# Microcontroller.net
KiCad netlist of a schematic drawn in EAGLE
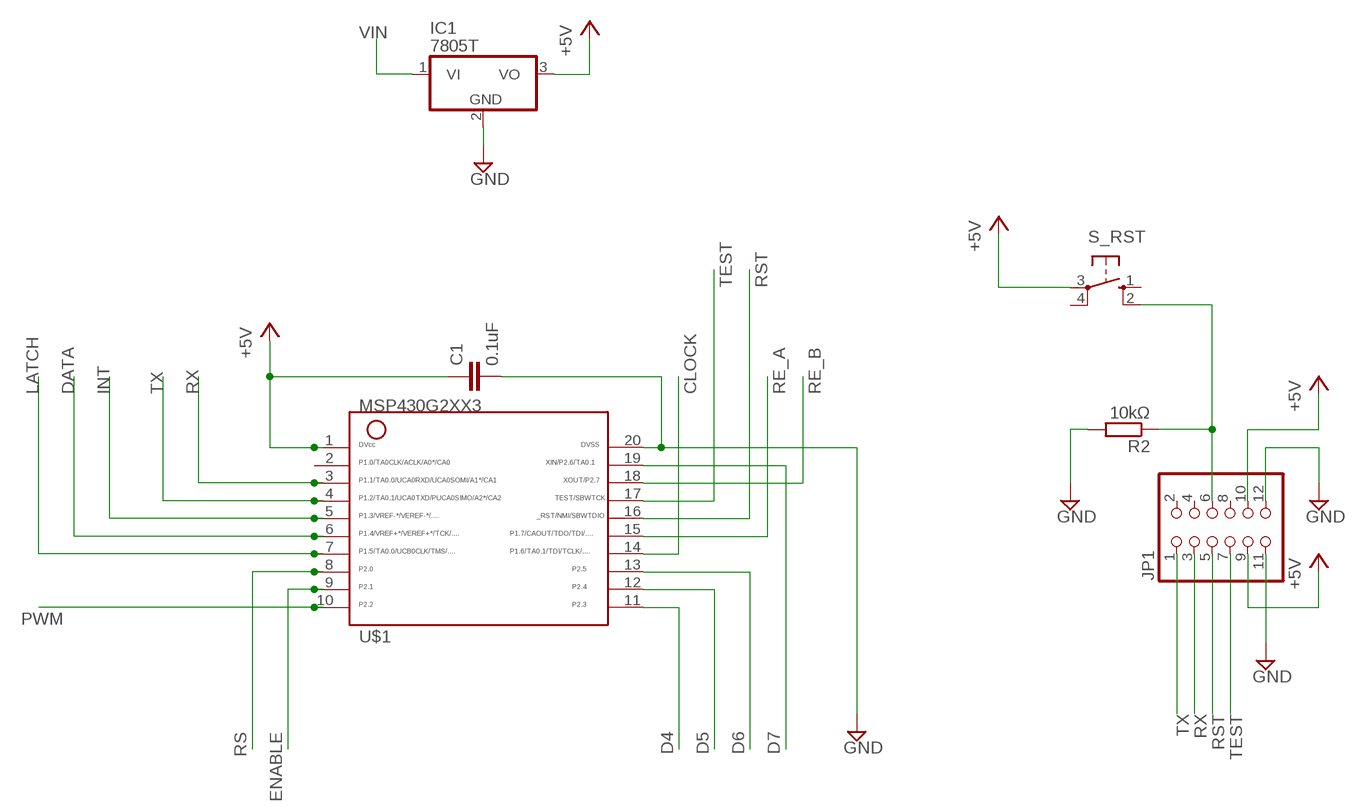
[diagram p0: schematic, sheet 1]

(export (version "E")
  (design (tool "Eeschema 10.0.6"))
  (components
    (comp (ref "C1")
      (value "0.1uF")
      (footprint "eagle-import:C025-025X050")
      (libsource (lib "eagle-import") (part "C-EU025-025X050"))
    )
    (comp (ref "IC1")
      (value "7805T")
      (footprint "eagle-import:TO220H")
      (libsource (lib "eagle-import") (part "78T05"))
    )
    (comp (ref "JP1")
      (value "PINHD-2X6")
      (footprint "eagle-import:2X06")
      (libsource (lib "eagle-import") (part "PINHD-2X6"))
    )
    (comp (ref "R2")
      (value "10kΩ")
      (footprint "eagle-import:0207_10")
      (libsource (lib "eagle-import") (part "R-EU_0207/10"))
    )
    (comp (ref "S_RST")
      (value "10-XX")
      (footprint "eagle-import:B3F-10XX")
      (fields (field (name "MPN") "B3F-1000"))
      (libsource (lib "eagle-import") (part "10-XX"))
    )
    (comp (ref "U$1")
      (value "G2XX3---N20")
      (footprint "eagle-import:N20")
      (libsource (lib "eagle-import") (part "G2XX3---N20"))
    )
  )
  (nets
    (net (code "1") (name "+5V") (class "Default")
      (node (ref "C1") (pin "1") (pinfunction "1_1") (pintype "passive"))
      (node (ref "IC1") (pin "3") (pinfunction "VO_3") (pintype "passive"))
      (node (ref "JP1") (pin "10") (pinfunction "10_10") (pintype "passive"))
      (node (ref "JP1") (pin "9") (pinfunction "9_9") (pintype "passive"))
      (node (ref "S_RST") (pin "3") (pinfunction "P_3") (pintype "passive"))
      (node (ref "U$1") (pin "1") (pinfunction "1_1") (pintype "bidirectional"))
    )
    (net (code "2") (name "/CLOCK") (class "Default")
      (node (ref "U$1") (pin "14") (pinfunction "14_14") (pintype "bidirectional"))
    )
    (net (code "3") (name "/D4") (class "Default")
      (node (ref "U$1") (pin "11") (pinfunction "11_11") (pintype "bidirectional"))
    )
    (net (code "4") (name "/D5") (class "Default")
      (node (ref "U$1") (pin "12") (pinfunction "12_12") (pintype "bidirectional"))
    )
    (net (code "5") (name "/D6") (class "Default")
      (node (ref "U$1") (pin "13") (pinfunction "13_13") (pintype "bidirectional"))
    )
    (net (code "6") (name "/D7") (class "Default")
      (node (ref "U$1") (pin "19") (pinfunction "19_19") (pintype "bidirectional"))
    )
    (net (code "7") (name "/DATA") (class "Default")
      (node (ref "U$1") (pin "6") (pinfunction "6_6") (pintype "bidirectional"))
    )
    (net (code "8") (name "/ENABLE") (class "Default")
      (node (ref "U$1") (pin "9") (pinfunction "9_9") (pintype "bidirectional"))
    )
    (net (code "9") (name "/INT") (class "Default")
      (node (ref "U$1") (pin "5") (pinfunction "5_5") (pintype "bidirectional"))
    )
    (net (code "10") (name "/LATCH") (class "Default")
      (node (ref "U$1") (pin "7") (pinfunction "7_7") (pintype "bidirectional"))
    )
    (net (code "11") (name "/PWM") (class "Default")
      (node (ref "U$1") (pin "10") (pinfunction "10_10") (pintype "bidirectional"))
    )
    (net (code "12") (name "/RE_A") (class "Default")
      (node (ref "U$1") (pin "15") (pinfunction "15_15") (pintype "bidirectional"))
    )
    (net (code "13") (name "/RE_B") (class "Default")
      (node (ref "U$1") (pin "18") (pinfunction "18_18") (pintype "bidirectional"))
    )
    (net (code "14") (name "/RS") (class "Default")
      (node (ref "U$1") (pin "8") (pinfunction "8_8") (pintype "bidirectional"))
    )
    (net (code "15") (name "/RST") (class "Default")
      (node (ref "JP1") (pin "5") (pinfunction "5_5") (pintype "passive"))
      (node (ref "U$1") (pin "16") (pinfunction "16_16") (pintype "bidirectional"))
    )
    (net (code "16") (name "/RX") (class "Default")
      (node (ref "JP1") (pin "3") (pinfunction "3_3") (pintype "passive"))
      (node (ref "U$1") (pin "3") (pinfunction "3_3") (pintype "bidirectional"))
    )
    (net (code "17") (name "/TEST") (class "Default")
      (node (ref "JP1") (pin "7") (pinfunction "7_7") (pintype "passive"))
      (node (ref "U$1") (pin "17") (pinfunction "17_17") (pintype "bidirectional"))
    )
    (net (code "18") (name "/TX") (class "Default")
      (node (ref "JP1") (pin "1") (pinfunction "1_1") (pintype "passive"))
      (node (ref "U$1") (pin "4") (pinfunction "4_4") (pintype "bidirectional"))
    )
    (net (code "19") (name "/VIN") (class "Default")
      (node (ref "IC1") (pin "1") (pinfunction "VI_1") (pintype "input"))
    )
    (net (code "20") (name "GND") (class "Default")
      (node (ref "C1") (pin "2") (pinfunction "2_2") (pintype "passive"))
      (node (ref "IC1") (pin "2") (pinfunction "GND_2") (pintype "passive"))
      (node (ref "JP1") (pin "11") (pinfunction "11_11") (pintype "passive"))
      (node (ref "JP1") (pin "12") (pinfunction "12_12") (pintype "passive"))
      (node (ref "R2") (pin "2") (pinfunction "2_2") (pintype "passive"))
      (node (ref "U$1") (pin "20") (pinfunction "20_20") (pintype "bidirectional"))
    )
    (net (code "21") (name "Net-(S_RST-S1)") (class "Default")
      (node (ref "JP1") (pin "6") (pinfunction "6_6") (pintype "passive"))
      (node (ref "R2") (pin "1") (pinfunction "1_1") (pintype "passive"))
      (node (ref "S_RST") (pin "2") (pinfunction "S1_2") (pintype "passive"))
    )
    (net (code "22") (name "unconnected-(JP1-Pad2)") (class "Default")
      (node (ref "JP1") (pin "2") (pinfunction "2_2") (pintype "passive"))
    )
    (net (code "23") (name "unconnected-(JP1-Pad4)") (class "Default")
      (node (ref "JP1") (pin "4") (pinfunction "4_4") (pintype "passive"))
    )
    (net (code "24") (name "unconnected-(JP1-Pad8)") (class "Default")
      (node (ref "JP1") (pin "8") (pinfunction "8_8") (pintype "passive"))
    )
    (net (code "25") (name "unconnected-(S_RST-P1-Pad4)") (class "Default")
      (node (ref "S_RST") (pin "4") (pinfunction "P1_4") (pintype "passive"))
    )
    (net (code "26") (name "unconnected-(S_RST-S-Pad1)") (class "Default")
      (node (ref "S_RST") (pin "1") (pinfunction "S_1") (pintype "passive"))
    )
    (net (code "27") (name "unconnected-(U$1-Pad2)") (class "Default")
      (node (ref "U$1") (pin "2") (pinfunction "2_2") (pintype "bidirectional"))
    )
  )
)
